# ModWheelsF19PCB.net
KiCad netlist of a schematic drawn in EAGLE
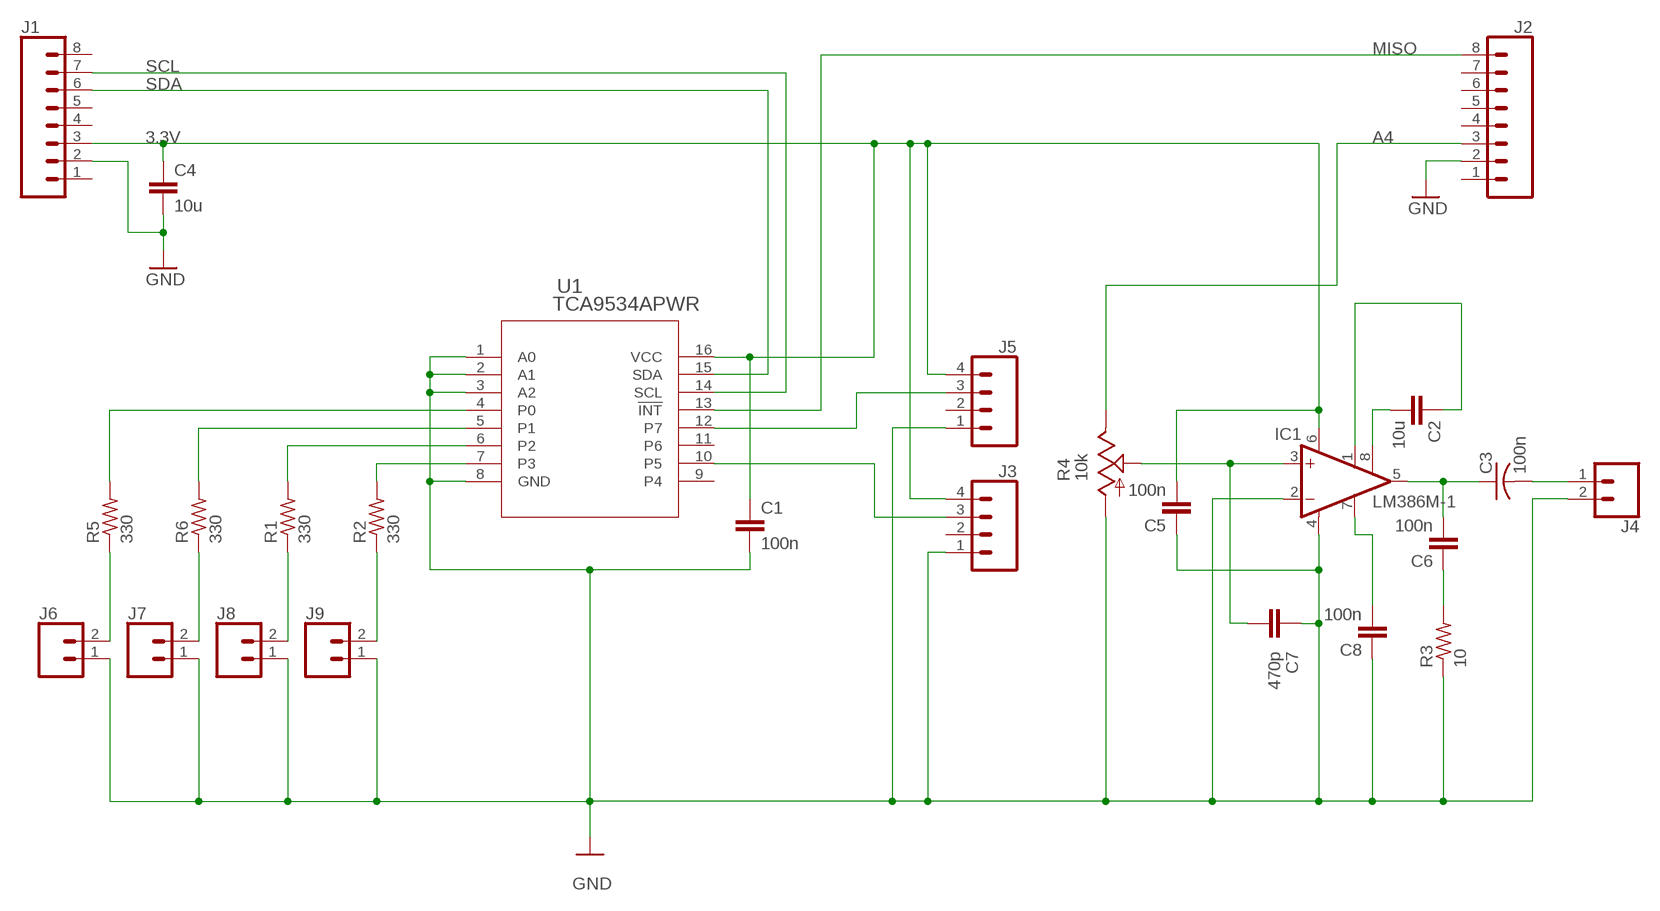
[diagram p0: schematic, sheet 1]

(export (version "E")
  (design (tool "Eeschema 10.0.6"))
  (components
    (comp (ref "C1")
      (value "100n")
      (footprint "eagle-import:C0805")
      (libsource (lib "eagle-import") (part "C-EUC0805"))
    )
    (comp (ref "C2")
      (value "10u")
      (footprint "eagle-import:C0805")
      (libsource (lib "eagle-import") (part "C-EUC0805"))
    )
    (comp (ref "C3")
      (value "100n")
      (footprint "eagle-import:C0805")
      (libsource (lib "eagle-import") (part "C-USC0805"))
    )
    (comp (ref "C4")
      (value "10u")
      (footprint "eagle-import:C0805")
      (libsource (lib "eagle-import") (part "C-EUC0805"))
    )
    (comp (ref "C5")
      (value "100n")
      (footprint "eagle-import:C0805")
      (libsource (lib "eagle-import") (part "C-EUC0805"))
    )
    (comp (ref "C6")
      (value "100n")
      (footprint "eagle-import:C0805")
      (libsource (lib "eagle-import") (part "C-EUC0805"))
    )
    (comp (ref "C7")
      (value "470p")
      (footprint "eagle-import:C0805")
      (libsource (lib "eagle-import") (part "C-EUC0805"))
    )
    (comp (ref "C8")
      (value "100n")
      (footprint "eagle-import:C0805")
      (libsource (lib "eagle-import") (part "C-EUC0805"))
    )
    (comp (ref "IC1")
      (value "LM386M-1")
      (footprint "eagle-import:SO08")
      (libsource (lib "eagle-import") (part "LM386?-M1"))
    )
    (comp (ref "J1")
      (value "CONN_08\"")
      (footprint "eagle-import:1X08")
      (libsource (lib "eagle-import") (part "CONN_08{dblquote}"))
    )
    (comp (ref "J2")
      (value "CONN_08\"")
      (footprint "eagle-import:1X08")
      (libsource (lib "eagle-import") (part "CONN_08{dblquote}"))
    )
    (comp (ref "J3")
      (value "CONN_04PTH")
      (footprint "eagle-import:1X04")
      (libsource (lib "eagle-import") (part "CONN_04PTH"))
    )
    (comp (ref "J4")
      (value "CONN_02")
      (footprint "eagle-import:1X02")
      (libsource (lib "eagle-import") (part "CONN_02"))
    )
    (comp (ref "J5")
      (value "CONN_04PTH")
      (footprint "eagle-import:1X04")
      (libsource (lib "eagle-import") (part "CONN_04PTH"))
    )
    (comp (ref "J6")
      (value "CONN_02")
      (footprint "eagle-import:1X02")
      (libsource (lib "eagle-import") (part "CONN_02"))
    )
    (comp (ref "J7")
      (value "CONN_02")
      (footprint "eagle-import:1X02")
      (libsource (lib "eagle-import") (part "CONN_02"))
    )
    (comp (ref "J8")
      (value "CONN_02")
      (footprint "eagle-import:1X02")
      (libsource (lib "eagle-import") (part "CONN_02"))
    )
    (comp (ref "J9")
      (value "CONN_02")
      (footprint "eagle-import:1X02")
      (libsource (lib "eagle-import") (part "CONN_02"))
    )
    (comp (ref "R1")
      (value "330")
      (footprint "eagle-import:R0805")
      (libsource (lib "eagle-import") (part "R-US_R0805"))
    )
    (comp (ref "R2")
      (value "330")
      (footprint "eagle-import:R0805")
      (libsource (lib "eagle-import") (part "R-US_R0805"))
    )
    (comp (ref "R3")
      (value "10")
      (footprint "eagle-import:R0805")
      (libsource (lib "eagle-import") (part "R-US_R0805"))
    )
    (comp (ref "R4")
      (value "10k")
      (footprint "eagle-import:S75P")
      (libsource (lib "eagle-import") (part "TRIM_US-S75P"))
    )
    (comp (ref "R5")
      (value "330")
      (footprint "eagle-import:R0805")
      (libsource (lib "eagle-import") (part "R-US_R0805"))
    )
    (comp (ref "R6")
      (value "330")
      (footprint "eagle-import:R0805")
      (libsource (lib "eagle-import") (part "R-US_R0805"))
    )
    (comp (ref "U1")
      (value "TCA9534APWR")
      (footprint "eagle-import:PW16")
      (libsource (lib "eagle-import") (part "TCA9534APWR"))
    )
  )
  (nets
    (net (code "1") (name "/3.3V") (class "Default")
      (node (ref "C1") (pin "1") (pinfunction "1_1") (pintype "passive"))
      (node (ref "C4") (pin "1") (pinfunction "1_1") (pintype "passive"))
      (node (ref "C5") (pin "2") (pinfunction "2_2") (pintype "passive"))
      (node (ref "IC1") (pin "6") (pinfunction "VS_6") (pintype "power_in"))
      (node (ref "J1") (pin "3") (pinfunction "3_3") (pintype "passive"))
      (node (ref "J3") (pin "4") (pinfunction "4_4") (pintype "passive"))
      (node (ref "J5") (pin "4") (pinfunction "4_4") (pintype "passive"))
      (node (ref "U1") (pin "16") (pinfunction "VCC_16") (pintype "power_in"))
    )
    (net (code "2") (name "/A4") (class "Default")
      (node (ref "J2") (pin "3") (pinfunction "3_3") (pintype "passive"))
      (node (ref "R4") (pin "E") (pinfunction "E_E") (pintype "passive"))
    )
    (net (code "3") (name "/MISO") (class "Default")
      (node (ref "J2") (pin "8") (pinfunction "8_8") (pintype "passive"))
      (node (ref "U1") (pin "13") (pinfunction "~{INT}_13") (pintype "output"))
    )
    (net (code "4") (name "/SCL") (class "Default")
      (node (ref "J1") (pin "7") (pinfunction "7_7") (pintype "passive"))
      (node (ref "U1") (pin "14") (pinfunction "SCL_14") (pintype "input"))
    )
    (net (code "5") (name "/SDA") (class "Default")
      (node (ref "J1") (pin "6") (pinfunction "6_6") (pintype "passive"))
      (node (ref "U1") (pin "15") (pinfunction "SDA_15") (pintype "bidirectional"))
    )
    (net (code "6") (name "GND") (class "Default")
      (node (ref "C1") (pin "2") (pinfunction "2_2") (pintype "passive"))
      (node (ref "C4") (pin "2") (pinfunction "2_2") (pintype "passive"))
      (node (ref "C5") (pin "1") (pinfunction "1_1") (pintype "passive"))
      (node (ref "C7") (pin "1") (pinfunction "1_1") (pintype "passive"))
      (node (ref "C8") (pin "1") (pinfunction "1_1") (pintype "passive"))
      (node (ref "IC1") (pin "2") (pinfunction "-IN_2") (pintype "input"))
      (node (ref "IC1") (pin "4") (pinfunction "GND_4") (pintype "power_in"))
      (node (ref "J1") (pin "2") (pinfunction "2_2") (pintype "passive"))
      (node (ref "J2") (pin "2") (pinfunction "2_2") (pintype "passive"))
      (node (ref "J3") (pin "1") (pinfunction "1_1") (pintype "passive"))
      (node (ref "J4") (pin "2") (pinfunction "2_2") (pintype "passive"))
      (node (ref "J5") (pin "1") (pinfunction "1_1") (pintype "passive"))
      (node (ref "J6") (pin "1") (pinfunction "1_1") (pintype "passive"))
      (node (ref "J7") (pin "1") (pinfunction "1_1") (pintype "passive"))
      (node (ref "J8") (pin "1") (pinfunction "1_1") (pintype "passive"))
      (node (ref "J9") (pin "1") (pinfunction "1_1") (pintype "passive"))
      (node (ref "R3") (pin "1") (pinfunction "1_1") (pintype "passive"))
      (node (ref "R4") (pin "A") (pinfunction "A_A") (pintype "passive"))
      (node (ref "U1") (pin "1") (pinfunction "A0_1") (pintype "input"))
      (node (ref "U1") (pin "2") (pinfunction "A1_2") (pintype "input"))
      (node (ref "U1") (pin "3") (pinfunction "A2_3") (pintype "input"))
      (node (ref "U1") (pin "8") (pinfunction "GND_8") (pintype "power_in"))
    )
    (net (code "7") (name "Net-(C2-Pad1)") (class "Default")
      (node (ref "C2") (pin "1") (pinfunction "1_1") (pintype "passive"))
      (node (ref "IC1") (pin "1") (pinfunction "GAIN_1") (pintype "passive"))
    )
    (net (code "8") (name "Net-(C2-Pad2)") (class "Default")
      (node (ref "C2") (pin "2") (pinfunction "2_2") (pintype "passive"))
      (node (ref "IC1") (pin "8") (pinfunction "GAIN_8") (pintype "passive"))
    )
    (net (code "9") (name "Net-(C3-Pad2)") (class "Default")
      (node (ref "C3") (pin "2") (pinfunction "2_2") (pintype "passive"))
      (node (ref "J4") (pin "1") (pinfunction "1_1") (pintype "passive"))
    )
    (net (code "10") (name "Net-(C6-Pad1)") (class "Default")
      (node (ref "C6") (pin "1") (pinfunction "1_1") (pintype "passive"))
      (node (ref "R3") (pin "2") (pinfunction "2_2") (pintype "passive"))
    )
    (net (code "11") (name "Net-(IC1-+IN)") (class "Default")
      (node (ref "C7") (pin "2") (pinfunction "2_2") (pintype "passive"))
      (node (ref "IC1") (pin "3") (pinfunction "+IN_3") (pintype "input"))
      (node (ref "R4") (pin "S") (pinfunction "S_S") (pintype "passive"))
    )
    (net (code "12") (name "Net-(IC1-BYPASS)") (class "Default")
      (node (ref "C8") (pin "2") (pinfunction "2_2") (pintype "passive"))
      (node (ref "IC1") (pin "7") (pinfunction "BYPASS_7") (pintype "passive"))
    )
    (net (code "13") (name "Net-(IC1-OUT)") (class "Default")
      (node (ref "C3") (pin "1") (pinfunction "1_1") (pintype "passive"))
      (node (ref "C6") (pin "2") (pinfunction "2_2") (pintype "passive"))
      (node (ref "IC1") (pin "5") (pinfunction "OUT_5") (pintype "output"))
    )
    (net (code "14") (name "Net-(J6-Pad2)") (class "Default")
      (node (ref "J6") (pin "2") (pinfunction "2_2") (pintype "passive"))
      (node (ref "R5") (pin "1") (pinfunction "1_1") (pintype "passive"))
    )
    (net (code "15") (name "Net-(J7-Pad2)") (class "Default")
      (node (ref "J7") (pin "2") (pinfunction "2_2") (pintype "passive"))
      (node (ref "R6") (pin "1") (pinfunction "1_1") (pintype "passive"))
    )
    (net (code "16") (name "Net-(J8-Pad2)") (class "Default")
      (node (ref "J8") (pin "2") (pinfunction "2_2") (pintype "passive"))
      (node (ref "R1") (pin "1") (pinfunction "1_1") (pintype "passive"))
    )
    (net (code "17") (name "Net-(J9-Pad2)") (class "Default")
      (node (ref "J9") (pin "2") (pinfunction "2_2") (pintype "passive"))
      (node (ref "R2") (pin "1") (pinfunction "1_1") (pintype "passive"))
    )
    (net (code "18") (name "Net-(U1-P0)") (class "Default")
      (node (ref "R5") (pin "2") (pinfunction "2_2") (pintype "passive"))
      (node (ref "U1") (pin "4") (pinfunction "P0_4") (pintype "bidirectional"))
    )
    (net (code "19") (name "Net-(U1-P1)") (class "Default")
      (node (ref "R6") (pin "2") (pinfunction "2_2") (pintype "passive"))
      (node (ref "U1") (pin "5") (pinfunction "P1_5") (pintype "bidirectional"))
    )
    (net (code "20") (name "Net-(U1-P2)") (class "Default")
      (node (ref "R1") (pin "2") (pinfunction "2_2") (pintype "passive"))
      (node (ref "U1") (pin "6") (pinfunction "P2_6") (pintype "bidirectional"))
    )
    (net (code "21") (name "Net-(U1-P3)") (class "Default")
      (node (ref "R2") (pin "2") (pinfunction "2_2") (pintype "passive"))
      (node (ref "U1") (pin "7") (pinfunction "P3_7") (pintype "bidirectional"))
    )
    (net (code "22") (name "Net-(U1-P5)") (class "Default")
      (node (ref "J3") (pin "3") (pinfunction "3_3") (pintype "passive"))
      (node (ref "U1") (pin "10") (pinfunction "P5_10") (pintype "bidirectional"))
    )
    (net (code "23") (name "Net-(U1-P7)") (class "Default")
      (node (ref "J5") (pin "3") (pinfunction "3_3") (pintype "passive"))
      (node (ref "U1") (pin "12") (pinfunction "P7_12") (pintype "bidirectional"))
    )
    (net (code "24") (name "unconnected-(J1-Pad1)") (class "Default")
      (node (ref "J1") (pin "1") (pinfunction "1_1") (pintype "passive"))
    )
    (net (code "25") (name "unconnected-(J1-Pad4)") (class "Default")
      (node (ref "J1") (pin "4") (pinfunction "4_4") (pintype "passive"))
    )
    (net (code "26") (name "unconnected-(J1-Pad5)") (class "Default")
      (node (ref "J1") (pin "5") (pinfunction "5_5") (pintype "passive"))
    )
    (net (code "27") (name "unconnected-(J1-Pad8)") (class "Default")
      (node (ref "J1") (pin "8") (pinfunction "8_8") (pintype "passive"))
    )
    (net (code "28") (name "unconnected-(J2-Pad1)") (class "Default")
      (node (ref "J2") (pin "1") (pinfunction "1_1") (pintype "passive"))
    )
    (net (code "29") (name "unconnected-(J2-Pad4)") (class "Default")
      (node (ref "J2") (pin "4") (pinfunction "4_4") (pintype "passive"))
    )
    (net (code "30") (name "unconnected-(J2-Pad5)") (class "Default")
      (node (ref "J2") (pin "5") (pinfunction "5_5") (pintype "passive"))
    )
    (net (code "31") (name "unconnected-(J2-Pad6)") (class "Default")
      (node (ref "J2") (pin "6") (pinfunction "6_6") (pintype "passive"))
    )
    (net (code "32") (name "unconnected-(J2-Pad7)") (class "Default")
      (node (ref "J2") (pin "7") (pinfunction "7_7") (pintype "passive"))
    )
    (net (code "33") (name "unconnected-(J3-Pad2)") (class "Default")
      (node (ref "J3") (pin "2") (pinfunction "2_2") (pintype "passive"))
    )
    (net (code "34") (name "unconnected-(J5-Pad2)") (class "Default")
      (node (ref "J5") (pin "2") (pinfunction "2_2") (pintype "passive"))
    )
    (net (code "35") (name "unconnected-(U1-P4-Pad9)") (class "Default")
      (node (ref "U1") (pin "9") (pinfunction "P4_9") (pintype "bidirectional"))
    )
    (net (code "36") (name "unconnected-(U1-P6-Pad11)") (class "Default")
      (node (ref "U1") (pin "11") (pinfunction "P6_11") (pintype "bidirectional"))
    )
  )
)
